# FIT_TCM_RJ45.net
KiCad netlist of a schematic drawn in Altium Designer
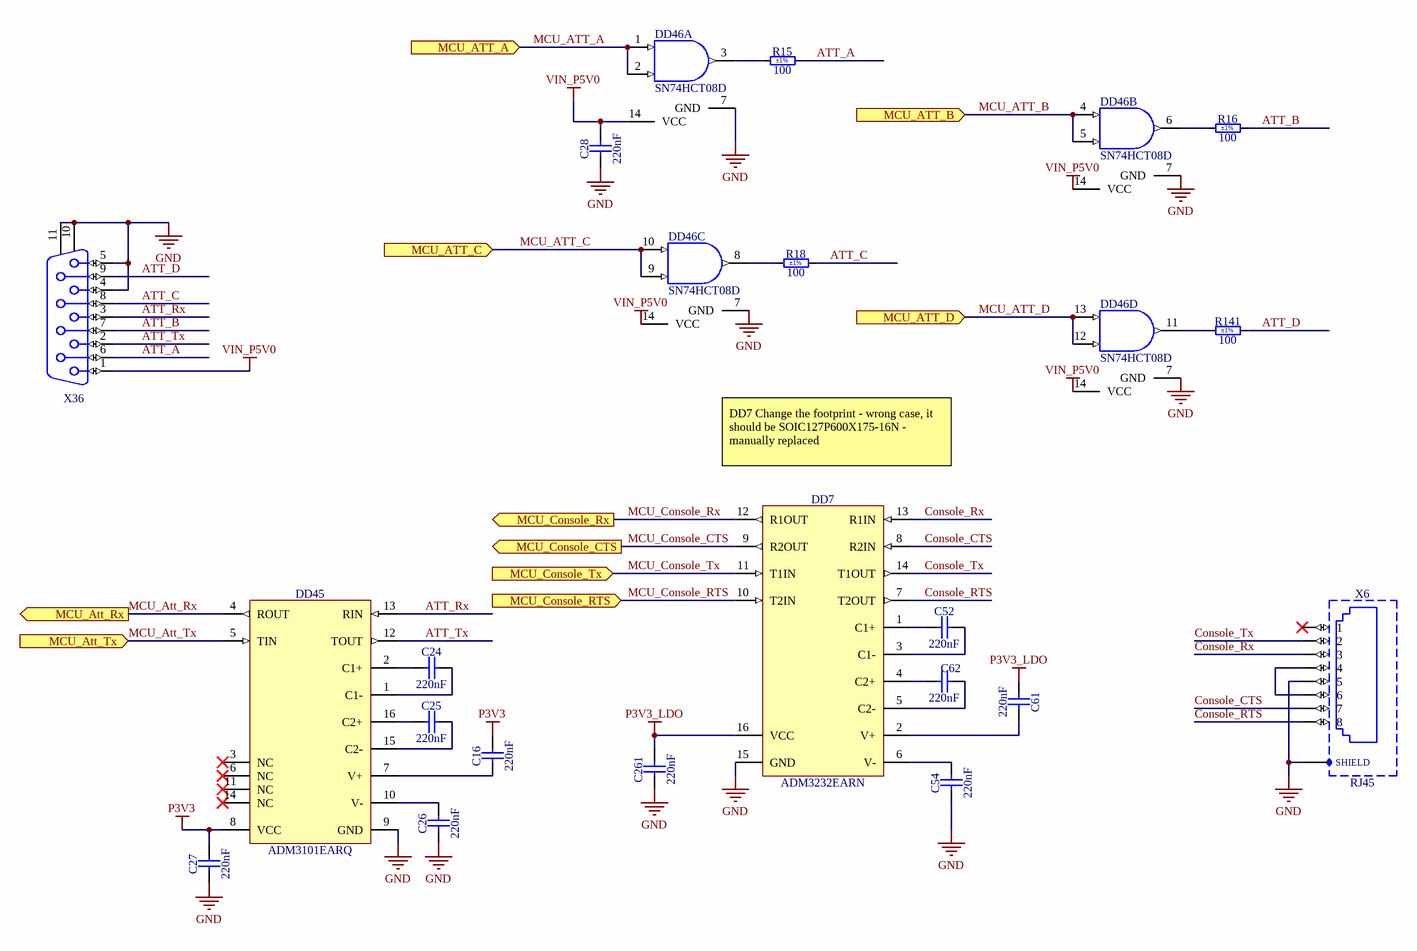
[diagram p0: FIT_TCM_RJ45.SchDoc]

(export (version "E")
  (design (tool "Eeschema 10.0.6"))
  (components
    (comp (ref "C16")
      (value "220nF")
      (footprint "CAPC2012X135N")
      (description "Non-polarised capacitor")
      (fields
        (field (name "PART NUMBER") "CC0805_220NF_50V_10%_X7R")
        (field (name "VOLTAGE") "50V")
        (field (name "AUTHOR") "CERN DEM JLC")
      )
      (libsource (lib "Capacitors") (part "Capacitor - non polarized"))
    )
    (comp (ref "C24")
      (value "220nF")
      (footprint "CAPC2012X135N")
      (description "Non-polarised capacitor")
      (fields
        (field (name "PART NUMBER") "CC0805_220NF_50V_10%_X7R")
        (field (name "VOLTAGE") "50V")
        (field (name "AUTHOR") "CERN DEM JLC")
      )
      (libsource (lib "Capacitors") (part "Capacitor - non polarized"))
    )
    (comp (ref "C25")
      (value "220nF")
      (footprint "CAPC2012X135N")
      (description "Non-polarised capacitor")
      (fields
        (field (name "PART NUMBER") "CC0805_220NF_50V_10%_X7R")
        (field (name "VOLTAGE") "50V")
        (field (name "AUTHOR") "CERN DEM JLC")
      )
      (libsource (lib "Capacitors") (part "Capacitor - non polarized"))
    )
    (comp (ref "C26")
      (value "220nF")
      (footprint "CAPC2012X135N")
      (description "Non-polarised capacitor")
      (fields
        (field (name "PART NUMBER") "CC0805_220NF_50V_10%_X7R")
        (field (name "VOLTAGE") "50V")
        (field (name "AUTHOR") "CERN DEM JLC")
      )
      (libsource (lib "Capacitors") (part "Capacitor - non polarized"))
    )
    (comp (ref "C27")
      (value "220nF")
      (footprint "CAPC2012X135N")
      (description "Non-polarised capacitor")
      (fields
        (field (name "PART NUMBER") "CC0805_220NF_50V_10%_X7R")
        (field (name "VOLTAGE") "50V")
        (field (name "AUTHOR") "CERN DEM JLC")
      )
      (libsource (lib "Capacitors") (part "Capacitor - non polarized"))
    )
    (comp (ref "C28")
      (value "220nF")
      (footprint "CAPC2012X135N")
      (description "Non-polarised capacitor")
      (fields
        (field (name "PART NUMBER") "CC0805_220NF_50V_10%_X7R")
        (field (name "VOLTAGE") "50V")
        (field (name "AUTHOR") "CERN DEM JLC")
      )
      (libsource (lib "Capacitors") (part "Capacitor - non polarized"))
    )
    (comp (ref "C52")
      (value "220nF")
      (footprint "CAPC2012X135N")
      (description "Non-polarised capacitor")
      (fields
        (field (name "PART NUMBER") "CC0805_220NF_50V_10%_X7R")
        (field (name "VOLTAGE") "50V")
        (field (name "AUTHOR") "CERN DEM JLC")
      )
      (libsource (lib "Capacitors") (part "Capacitor - non polarized"))
    )
    (comp (ref "C54")
      (value "220nF")
      (footprint "CAPC2012X135N")
      (description "Non-polarised capacitor")
      (fields
        (field (name "PART NUMBER") "CC0805_220NF_50V_10%_X7R")
        (field (name "VOLTAGE") "50V")
        (field (name "AUTHOR") "CERN DEM JLC")
      )
      (libsource (lib "Capacitors") (part "Capacitor - non polarized"))
    )
    (comp (ref "C61")
      (value "220nF")
      (footprint "CAPC2012X135N")
      (description "Non-polarised capacitor")
      (fields
        (field (name "PART NUMBER") "CC0805_220NF_50V_10%_X7R")
        (field (name "VOLTAGE") "50V")
        (field (name "AUTHOR") "CERN DEM JLC")
      )
      (libsource (lib "Capacitors") (part "Capacitor - non polarized"))
    )
    (comp (ref "C62")
      (value "220nF")
      (footprint "CAPC2012X135N")
      (description "Non-polarised capacitor")
      (fields
        (field (name "PART NUMBER") "CC0805_220NF_50V_10%_X7R")
        (field (name "VOLTAGE") "50V")
        (field (name "AUTHOR") "CERN DEM JLC")
      )
      (libsource (lib "Capacitors") (part "Capacitor - non polarized"))
    )
    (comp (ref "C261")
      (value "220nF")
      (footprint "CAPC2012X135N")
      (description "Non-polarised capacitor")
      (fields
        (field (name "PART NUMBER") "CC0805_220NF_50V_10%_X7R")
        (field (name "VOLTAGE") "50V")
        (field (name "AUTHOR") "CERN DEM JLC")
      )
      (libsource (lib "Capacitors") (part "Capacitor - non polarized"))
    )
    (comp (ref "DD7")
      (value "ADM3232EARN")
      (footprint "SOIC127P600X175-16N")
      (description "±15 kV ESD Protected, 3.3 V, RS-232 Line Driver/Receiver")
      (fields (field (name "MANUFACTURER") "ANALOG DEVICES") (field (name "AUTHOR") "CERN DEM HF"))
      (libsource (lib "ICs And Semiconductors") (part "ADM3232EARN"))
    )
    (comp (ref "DD45")
      (value "ADM3101EARQ")
      (footprint "SOP63P600X175-16N")
      (description "±15 kV ESD Protected, 3.3 V Single-Channel RS-232 Line Driver/Receiver")
      (fields (field (name "MANUFACTURER") "ANALOG DEVICES") (field (name "AUTHOR") "CERN DEM HF"))
      (libsource (lib "ICs And Semiconductors") (part "ADM3101EARQ"))
    )
    (comp (ref "DD46")
      (value "SN74HCT08D")
      (footprint "SOIC127P600X175-14N")
      (description "Quad 2-Input AND Gate")
      (fields (field (name "MANUFACTURER") "TEXAS INSTRUMENTS") (field (name "AUTHOR") "CERN DEM HF"))
      (libsource (lib "ICs And Semiconductors") (part "7408"))
    )
    (comp (ref "R15")
      (value "100")
      (footprint "RESC2012X60N")
      (description "Resistor - 1%")
      (fields
        (field (name "TOLERANCE") "±1%")
        (field (name "PART NUMBER") "R0805_100R_1%_0.125W_100PPM")
        (field (name "POWER") "0.125W")
        (field (name "AUTHOR") "CERN DEM JLC")
      )
      (libsource (lib "Resistors") (part "Resistor - 1%"))
    )
    (comp (ref "R16")
      (value "100")
      (footprint "RESC2012X60N")
      (description "Resistor - 1%")
      (fields
        (field (name "TOLERANCE") "±1%")
        (field (name "PART NUMBER") "R0805_100R_1%_0.125W_100PPM")
        (field (name "POWER") "0.125W")
        (field (name "AUTHOR") "CERN DEM JLC")
      )
      (libsource (lib "Resistors") (part "Resistor - 1%"))
    )
    (comp (ref "R18")
      (value "100")
      (footprint "RESC2012X60N")
      (description "Resistor - 1%")
      (fields
        (field (name "TOLERANCE") "±1%")
        (field (name "PART NUMBER") "R0805_100R_1%_0.125W_100PPM")
        (field (name "POWER") "0.125W")
        (field (name "AUTHOR") "CERN DEM JLC")
      )
      (libsource (lib "Resistors") (part "Resistor - 1%"))
    )
    (comp (ref "R141")
      (value "100")
      (footprint "RESC2012X60N")
      (description "Resistor - 1%")
      (fields
        (field (name "TOLERANCE") "±1%")
        (field (name "PART NUMBER") "R0805_100R_1%_0.125W_100PPM")
        (field (name "POWER") "0.125W")
        (field (name "AUTHOR") "CERN DEM JLC")
      )
      (libsource (lib "Resistors") (part "Resistor - 1%"))
    )
    (comp (ref "X6")
      (value "RJ45")
      (footprint "AMPHENOL_RJLSE4238101")
      (description "Connector RJ45 + Shield")
      (fields
        (field (name "PART NUMBER") "AMPHENOL_RJLSE4238101")
        (field (name "MANUFACTURER") "AMPHENOL")
        (field (name "AUTHOR") "CERN DEM HF")
      )
      (libsource (lib "Connectors") (part "Connector RJ45 + Shield"))
    )
    (comp (ref "X36")
      (value "D-Sub 9F")
      (footprint "HARTING_09 66 152 6612")
      (description "Connector D-sub 9 Female")
      (fields
        (field (name "PART NUMBER") "HARTING_09 66 152 6612")
        (field (name "MANUFACTURER") "HARTING")
        (field (name "AUTHOR") "CERN DEM JLC")
      )
      (libsource (lib "Connectors") (part "Connector D-sub 9 Female"))
    )
  )
  (nets
    (net (code "1") (name "/ATT_A") (class "Default")
      (node (ref "R15") (pin "2") (pinfunction "2_2") (pintype "passive"))
      (node (ref "X36") (pin "6") (pinfunction "6_6") (pintype "bidirectional"))
    )
    (net (code "2") (name "/ATT_B") (class "Default")
      (node (ref "R16") (pin "2") (pinfunction "2_2") (pintype "passive"))
      (node (ref "X36") (pin "7") (pinfunction "7_7") (pintype "bidirectional"))
    )
    (net (code "3") (name "/ATT_C") (class "Default")
      (node (ref "R18") (pin "2") (pinfunction "2_2") (pintype "passive"))
      (node (ref "X36") (pin "8") (pinfunction "8_8") (pintype "bidirectional"))
    )
    (net (code "4") (name "/ATT_D") (class "Default")
      (node (ref "R141") (pin "2") (pinfunction "2_2") (pintype "passive"))
      (node (ref "X36") (pin "9") (pinfunction "9_9") (pintype "bidirectional"))
    )
    (net (code "5") (name "/ATT_Rx") (class "Default")
      (node (ref "DD45") (pin "13") (pinfunction "RIN_13") (pintype "input"))
      (node (ref "X36") (pin "3") (pinfunction "3_3") (pintype "bidirectional"))
    )
    (net (code "6") (name "/ATT_Tx") (class "Default")
      (node (ref "DD45") (pin "12") (pinfunction "TOUT_12") (pintype "output"))
      (node (ref "X36") (pin "2") (pinfunction "2_2") (pintype "bidirectional"))
    )
    (net (code "7") (name "/Console_CTS") (class "Default")
      (node (ref "DD7") (pin "8") (pinfunction "R2IN_8") (pintype "input"))
      (node (ref "X6") (pin "7") (pinfunction "7_7") (pintype "bidirectional"))
    )
    (net (code "8") (name "/Console_RTS") (class "Default")
      (node (ref "DD7") (pin "7") (pinfunction "T2OUT_7") (pintype "output"))
      (node (ref "X6") (pin "8") (pinfunction "8_8") (pintype "bidirectional"))
    )
    (net (code "9") (name "/Console_Rx") (class "Default")
      (node (ref "DD7") (pin "13") (pinfunction "R1IN_13") (pintype "input"))
      (node (ref "X6") (pin "3") (pinfunction "3_3") (pintype "bidirectional"))
    )
    (net (code "10") (name "/Console_Tx") (class "Default")
      (node (ref "DD7") (pin "14") (pinfunction "T1OUT_14") (pintype "output"))
      (node (ref "X6") (pin "2") (pinfunction "2_2") (pintype "bidirectional"))
    )
    (net (code "11") (name "/MCU_ATT_A") (class "Default")
      (node (ref "DD46") (pin "1") (pinfunction "A_1") (pintype "input"))
      (node (ref "DD46") (pin "2") (pinfunction "B_2") (pintype "input"))
    )
    (net (code "12") (name "/MCU_ATT_B") (class "Default")
      (node (ref "DD46") (pin "4") (pinfunction "A_4") (pintype "input"))
      (node (ref "DD46") (pin "5") (pinfunction "B_5") (pintype "input"))
    )
    (net (code "13") (name "/MCU_ATT_C") (class "Default")
      (node (ref "DD46") (pin "10") (pinfunction "A_10") (pintype "input"))
      (node (ref "DD46") (pin "9") (pinfunction "B_9") (pintype "input"))
    )
    (net (code "14") (name "/MCU_ATT_D") (class "Default")
      (node (ref "DD46") (pin "12") (pinfunction "B_12") (pintype "input"))
      (node (ref "DD46") (pin "13") (pinfunction "A_13") (pintype "input"))
    )
    (net (code "15") (name "/MCU_Att_Rx") (class "Default")
      (node (ref "DD45") (pin "4") (pinfunction "ROUT_4") (pintype "output"))
    )
    (net (code "16") (name "/MCU_Att_Tx") (class "Default")
      (node (ref "DD45") (pin "5") (pinfunction "TIN_5") (pintype "input"))
    )
    (net (code "17") (name "/MCU_Console_CTS") (class "Default")
      (node (ref "DD7") (pin "9") (pinfunction "R2OUT_9") (pintype "output"))
    )
    (net (code "18") (name "/MCU_Console_RTS") (class "Default")
      (node (ref "DD7") (pin "10") (pinfunction "T2IN_10") (pintype "input"))
    )
    (net (code "19") (name "/MCU_Console_Rx") (class "Default")
      (node (ref "DD7") (pin "12") (pinfunction "R1OUT_12") (pintype "output"))
    )
    (net (code "20") (name "/MCU_Console_Tx") (class "Default")
      (node (ref "DD7") (pin "11") (pinfunction "T1IN_11") (pintype "input"))
    )
    (net (code "21") (name "GND") (class "Default")
      (node (ref "C26") (pin "1") (pinfunction "1_1") (pintype "passive"))
      (node (ref "C261") (pin "1") (pinfunction "1_1") (pintype "passive"))
      (node (ref "C27") (pin "1") (pinfunction "1_1") (pintype "passive"))
      (node (ref "C28") (pin "1") (pinfunction "1_1") (pintype "passive"))
      (node (ref "C54") (pin "1") (pinfunction "1_1") (pintype "passive"))
      (node (ref "DD45") (pin "9") (pinfunction "GND_9") (pintype "power_in"))
      (node (ref "DD46") (pin "7") (pinfunction "GND_7") (pintype "power_in"))
      (node (ref "DD7") (pin "15") (pinfunction "GND_15") (pintype "power_in"))
      (node (ref "X36") (pin "10") (pinfunction "10_10") (pintype "passive"))
      (node (ref "X36") (pin "11") (pinfunction "11_11") (pintype "passive"))
      (node (ref "X36") (pin "4") (pinfunction "4_4") (pintype "bidirectional"))
      (node (ref "X36") (pin "5") (pinfunction "5_5") (pintype "bidirectional"))
      (node (ref "X6") (pin "5") (pinfunction "5_5") (pintype "bidirectional"))
      (node (ref "X6") (pin "SHIELD") (pinfunction "SHIELD_SHIELD") (pintype "passive"))
    )
    (net (code "22") (name "Net-(DD7-C1+)") (class "Default")
      (node (ref "C52") (pin "1") (pinfunction "1_1") (pintype "passive"))
      (node (ref "DD7") (pin "1") (pinfunction "C1+_1") (pintype "passive"))
    )
    (net (code "23") (name "Net-(DD7-C1-)") (class "Default")
      (node (ref "C52") (pin "2") (pinfunction "2_2") (pintype "passive"))
      (node (ref "DD7") (pin "3") (pinfunction "C1-_3") (pintype "passive"))
    )
    (net (code "24") (name "Net-(DD7-C2+)") (class "Default")
      (node (ref "C62") (pin "1") (pinfunction "1_1") (pintype "passive"))
      (node (ref "DD7") (pin "4") (pinfunction "C2+_4") (pintype "passive"))
    )
    (net (code "25") (name "Net-(DD7-C2-)") (class "Default")
      (node (ref "C62") (pin "2") (pinfunction "2_2") (pintype "passive"))
      (node (ref "DD7") (pin "5") (pinfunction "C2-_5") (pintype "passive"))
    )
    (net (code "26") (name "Net-(DD7-V+)") (class "Default")
      (node (ref "C61") (pin "2") (pinfunction "2_2") (pintype "passive"))
      (node (ref "DD7") (pin "2") (pinfunction "V+_2") (pintype "power_in"))
    )
    (net (code "27") (name "Net-(DD7-V-)") (class "Default")
      (node (ref "C54") (pin "2") (pinfunction "2_2") (pintype "passive"))
      (node (ref "DD7") (pin "6") (pinfunction "V-_6") (pintype "power_in"))
    )
    (net (code "28") (name "Net-(DD45-C1+)") (class "Default")
      (node (ref "C24") (pin "1") (pinfunction "1_1") (pintype "passive"))
      (node (ref "DD45") (pin "2") (pinfunction "C1+_2") (pintype "passive"))
    )
    (net (code "29") (name "Net-(DD45-C1-)") (class "Default")
      (node (ref "C24") (pin "2") (pinfunction "2_2") (pintype "passive"))
      (node (ref "DD45") (pin "1") (pinfunction "C1-_1") (pintype "passive"))
    )
    (net (code "30") (name "Net-(DD45-C2+)") (class "Default")
      (node (ref "C25") (pin "1") (pinfunction "1_1") (pintype "passive"))
      (node (ref "DD45") (pin "16") (pinfunction "C2+_16") (pintype "passive"))
    )
    (net (code "31") (name "Net-(DD45-C2-)") (class "Default")
      (node (ref "C25") (pin "2") (pinfunction "2_2") (pintype "passive"))
      (node (ref "DD45") (pin "15") (pinfunction "C2-_15") (pintype "passive"))
    )
    (net (code "32") (name "Net-(DD45-V+)") (class "Default")
      (node (ref "C16") (pin "1") (pinfunction "1_1") (pintype "passive"))
      (node (ref "DD45") (pin "7") (pinfunction "V+_7") (pintype "power_in"))
    )
    (net (code "33") (name "Net-(DD45-V-)") (class "Default")
      (node (ref "C26") (pin "2") (pinfunction "2_2") (pintype "passive"))
      (node (ref "DD45") (pin "10") (pinfunction "V-_10") (pintype "power_in"))
    )
    (net (code "34") (name "Net-(DD46A-Y)") (class "Default")
      (node (ref "DD46") (pin "3") (pinfunction "Y_3") (pintype "output"))
      (node (ref "R15") (pin "1") (pinfunction "1_1") (pintype "passive"))
    )
    (net (code "35") (name "Net-(DD46B-Y)") (class "Default")
      (node (ref "DD46") (pin "6") (pinfunction "Y_6") (pintype "output"))
      (node (ref "R16") (pin "1") (pinfunction "1_1") (pintype "passive"))
    )
    (net (code "36") (name "Net-(DD46C-Y)") (class "Default")
      (node (ref "DD46") (pin "8") (pinfunction "Y_8") (pintype "output"))
      (node (ref "R18") (pin "1") (pinfunction "1_1") (pintype "passive"))
    )
    (net (code "37") (name "Net-(DD46D-Y)") (class "Default")
      (node (ref "DD46") (pin "11") (pinfunction "Y_11") (pintype "output"))
      (node (ref "R141") (pin "1") (pinfunction "1_1") (pintype "passive"))
    )
    (net (code "38") (name "Net-(X6-Pad4)") (class "Default")
      (node (ref "X6") (pin "4") (pinfunction "4_4") (pintype "bidirectional"))
      (node (ref "X6") (pin "6") (pinfunction "6_6") (pintype "bidirectional"))
    )
    (net (code "39") (name "P3V3") (class "Default")
      (node (ref "C16") (pin "2") (pinfunction "2_2") (pintype "passive"))
      (node (ref "C27") (pin "2") (pinfunction "2_2") (pintype "passive"))
      (node (ref "DD45") (pin "8") (pinfunction "VCC_8") (pintype "power_in"))
    )
    (net (code "40") (name "P3V3_LDO") (class "Default")
      (node (ref "C261") (pin "2") (pinfunction "2_2") (pintype "passive"))
      (node (ref "C61") (pin "1") (pinfunction "1_1") (pintype "passive"))
      (node (ref "DD7") (pin "16") (pinfunction "VCC_16") (pintype "power_in"))
    )
    (net (code "41") (name "VIN_P5V0") (class "Default")
      (node (ref "C28") (pin "2") (pinfunction "2_2") (pintype "passive"))
      (node (ref "DD46") (pin "14") (pinfunction "VCC_14") (pintype "power_in"))
      (node (ref "X36") (pin "1") (pinfunction "1_1") (pintype "bidirectional"))
    )
    (net (code "42") (name "unconnected-(DD45-NC-Pad3)") (class "Default")
      (node (ref "DD45") (pin "3") (pinfunction "NC_3") (pintype "passive+no_connect"))
    )
    (net (code "43") (name "unconnected-(DD45-NC-Pad6)") (class "Default")
      (node (ref "DD45") (pin "6") (pinfunction "NC_6") (pintype "power_in+no_connect"))
    )
    (net (code "44") (name "unconnected-(DD45-NC-Pad11)") (class "Default")
      (node (ref "DD45") (pin "11") (pinfunction "NC_11") (pintype "power_in+no_connect"))
    )
    (net (code "45") (name "unconnected-(DD45-NC-Pad14)") (class "Default")
      (node (ref "DD45") (pin "14") (pinfunction "NC_14") (pintype "power_in+no_connect"))
    )
    (net (code "46") (name "unconnected-(X6-Pad1)") (class "Default")
      (node (ref "X6") (pin "1") (pinfunction "1_1") (pintype "bidirectional+no_connect"))
    )
  )
)
